# mister_io_todb9.net
KiCad netlist of a schematic drawn in EAGLE
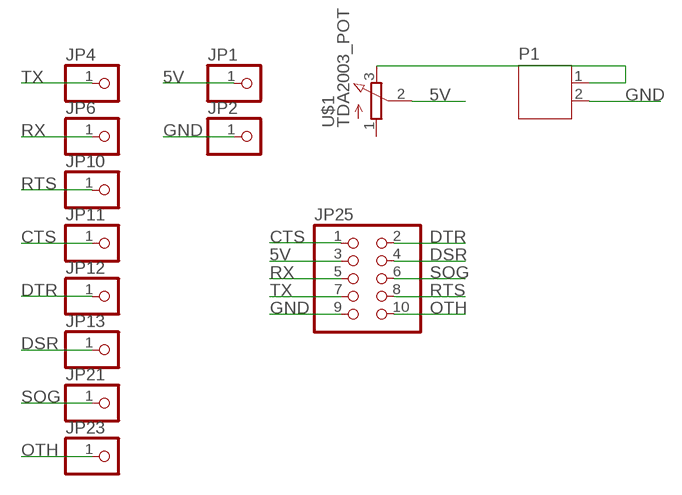
[diagram p0: schematic, sheet 1]

(export (version "E")
  (design (tool "Eeschema 10.0.6"))
  (components
    (comp (ref "JP1")
      (value "PINHD-1X1")
      (footprint "eagle-import:1X01")
      (libsource (lib "eagle-import") (part "PINHD-1X1"))
    )
    (comp (ref "JP2")
      (value "PINHD-1X1")
      (footprint "eagle-import:1X01")
      (libsource (lib "eagle-import") (part "PINHD-1X1"))
    )
    (comp (ref "JP4")
      (value "PINHD-1X1")
      (footprint "eagle-import:1X01")
      (libsource (lib "eagle-import") (part "PINHD-1X1"))
    )
    (comp (ref "JP6")
      (value "PINHD-1X1")
      (footprint "eagle-import:1X01")
      (libsource (lib "eagle-import") (part "PINHD-1X1"))
    )
    (comp (ref "JP10")
      (value "PINHD-1X1")
      (footprint "eagle-import:1X01")
      (libsource (lib "eagle-import") (part "PINHD-1X1"))
    )
    (comp (ref "JP11")
      (value "PINHD-1X1")
      (footprint "eagle-import:1X01")
      (libsource (lib "eagle-import") (part "PINHD-1X1"))
    )
    (comp (ref "JP12")
      (value "PINHD-1X1")
      (footprint "eagle-import:1X01")
      (libsource (lib "eagle-import") (part "PINHD-1X1"))
    )
    (comp (ref "JP13")
      (value "PINHD-1X1")
      (footprint "eagle-import:1X01")
      (libsource (lib "eagle-import") (part "PINHD-1X1"))
    )
    (comp (ref "JP21")
      (value "PINHD-1X1")
      (footprint "eagle-import:1X01")
      (libsource (lib "eagle-import") (part "PINHD-1X1"))
    )
    (comp (ref "JP23")
      (value "PINHD-1X1")
      (footprint "eagle-import:1X01")
      (libsource (lib "eagle-import") (part "PINHD-1X1"))
    )
    (comp (ref "JP25")
      (value "PINHD-2X5")
      (footprint "eagle-import:2X05")
      (libsource (lib "eagle-import") (part "PINHD-2X5"))
    )
    (comp (ref "P1")
      (value "JST-PH2")
      (footprint "eagle-import:JST-PH2")
      (libsource (lib "eagle-import") (part "JST-PH2"))
    )
    (comp (ref "U$1")
      (value "TDA2003_POT")
      (footprint "eagle-import:TDA2003_POT")
      (libsource (lib "eagle-import") (part "TDA2003_POT"))
    )
  )
  (nets
    (net (code "1") (name "/5V") (class "Default")
      (node (ref "JP1") (pin "1") (pinfunction "1_1") (pintype "passive"))
      (node (ref "JP25") (pin "3") (pinfunction "3_3") (pintype "passive"))
      (node (ref "U$1") (pin "2") (pinfunction "S_2") (pintype "passive"))
    )
    (net (code "2") (name "/CTS") (class "Default")
      (node (ref "JP11") (pin "1") (pinfunction "1_1") (pintype "passive"))
      (node (ref "JP25") (pin "1") (pinfunction "1_1") (pintype "passive"))
    )
    (net (code "3") (name "/DSR") (class "Default")
      (node (ref "JP13") (pin "1") (pinfunction "1_1") (pintype "passive"))
      (node (ref "JP25") (pin "4") (pinfunction "4_4") (pintype "passive"))
    )
    (net (code "4") (name "/DTR") (class "Default")
      (node (ref "JP12") (pin "1") (pinfunction "1_1") (pintype "passive"))
      (node (ref "JP25") (pin "2") (pinfunction "2_2") (pintype "passive"))
    )
    (net (code "5") (name "/GND") (class "Default")
      (node (ref "JP2") (pin "1") (pinfunction "1_1") (pintype "passive"))
      (node (ref "JP25") (pin "9") (pinfunction "9_9") (pintype "passive"))
      (node (ref "P1") (pin "2") (pinfunction "2_2") (pintype "passive"))
    )
    (net (code "6") (name "/OTH") (class "Default")
      (node (ref "JP23") (pin "1") (pinfunction "1_1") (pintype "passive"))
      (node (ref "JP25") (pin "10") (pinfunction "10_10") (pintype "passive"))
    )
    (net (code "7") (name "/RTS") (class "Default")
      (node (ref "JP10") (pin "1") (pinfunction "1_1") (pintype "passive"))
      (node (ref "JP25") (pin "8") (pinfunction "8_8") (pintype "passive"))
    )
    (net (code "8") (name "/RX") (class "Default")
      (node (ref "JP25") (pin "5") (pinfunction "5_5") (pintype "passive"))
      (node (ref "JP6") (pin "1") (pinfunction "1_1") (pintype "passive"))
    )
    (net (code "9") (name "/SOG") (class "Default")
      (node (ref "JP21") (pin "1") (pinfunction "1_1") (pintype "passive"))
      (node (ref "JP25") (pin "6") (pinfunction "6_6") (pintype "passive"))
    )
    (net (code "10") (name "/TX") (class "Default")
      (node (ref "JP25") (pin "7") (pinfunction "7_7") (pintype "passive"))
      (node (ref "JP4") (pin "1") (pinfunction "1_1") (pintype "passive"))
    )
    (net (code "11") (name "Net-(U$1-E)") (class "Default")
      (node (ref "P1") (pin "1") (pinfunction "1_1") (pintype "passive"))
      (node (ref "U$1") (pin "3") (pinfunction "E_3") (pintype "passive"))
    )
    (net (code "12") (name "unconnected-(U$1-A-Pad1)") (class "Default")
      (node (ref "U$1") (pin "1") (pinfunction "A_1") (pintype "passive"))
    )
  )
)
